# L6726a-5v.net
KiCad netlist of a schematic drawn in EAGLE
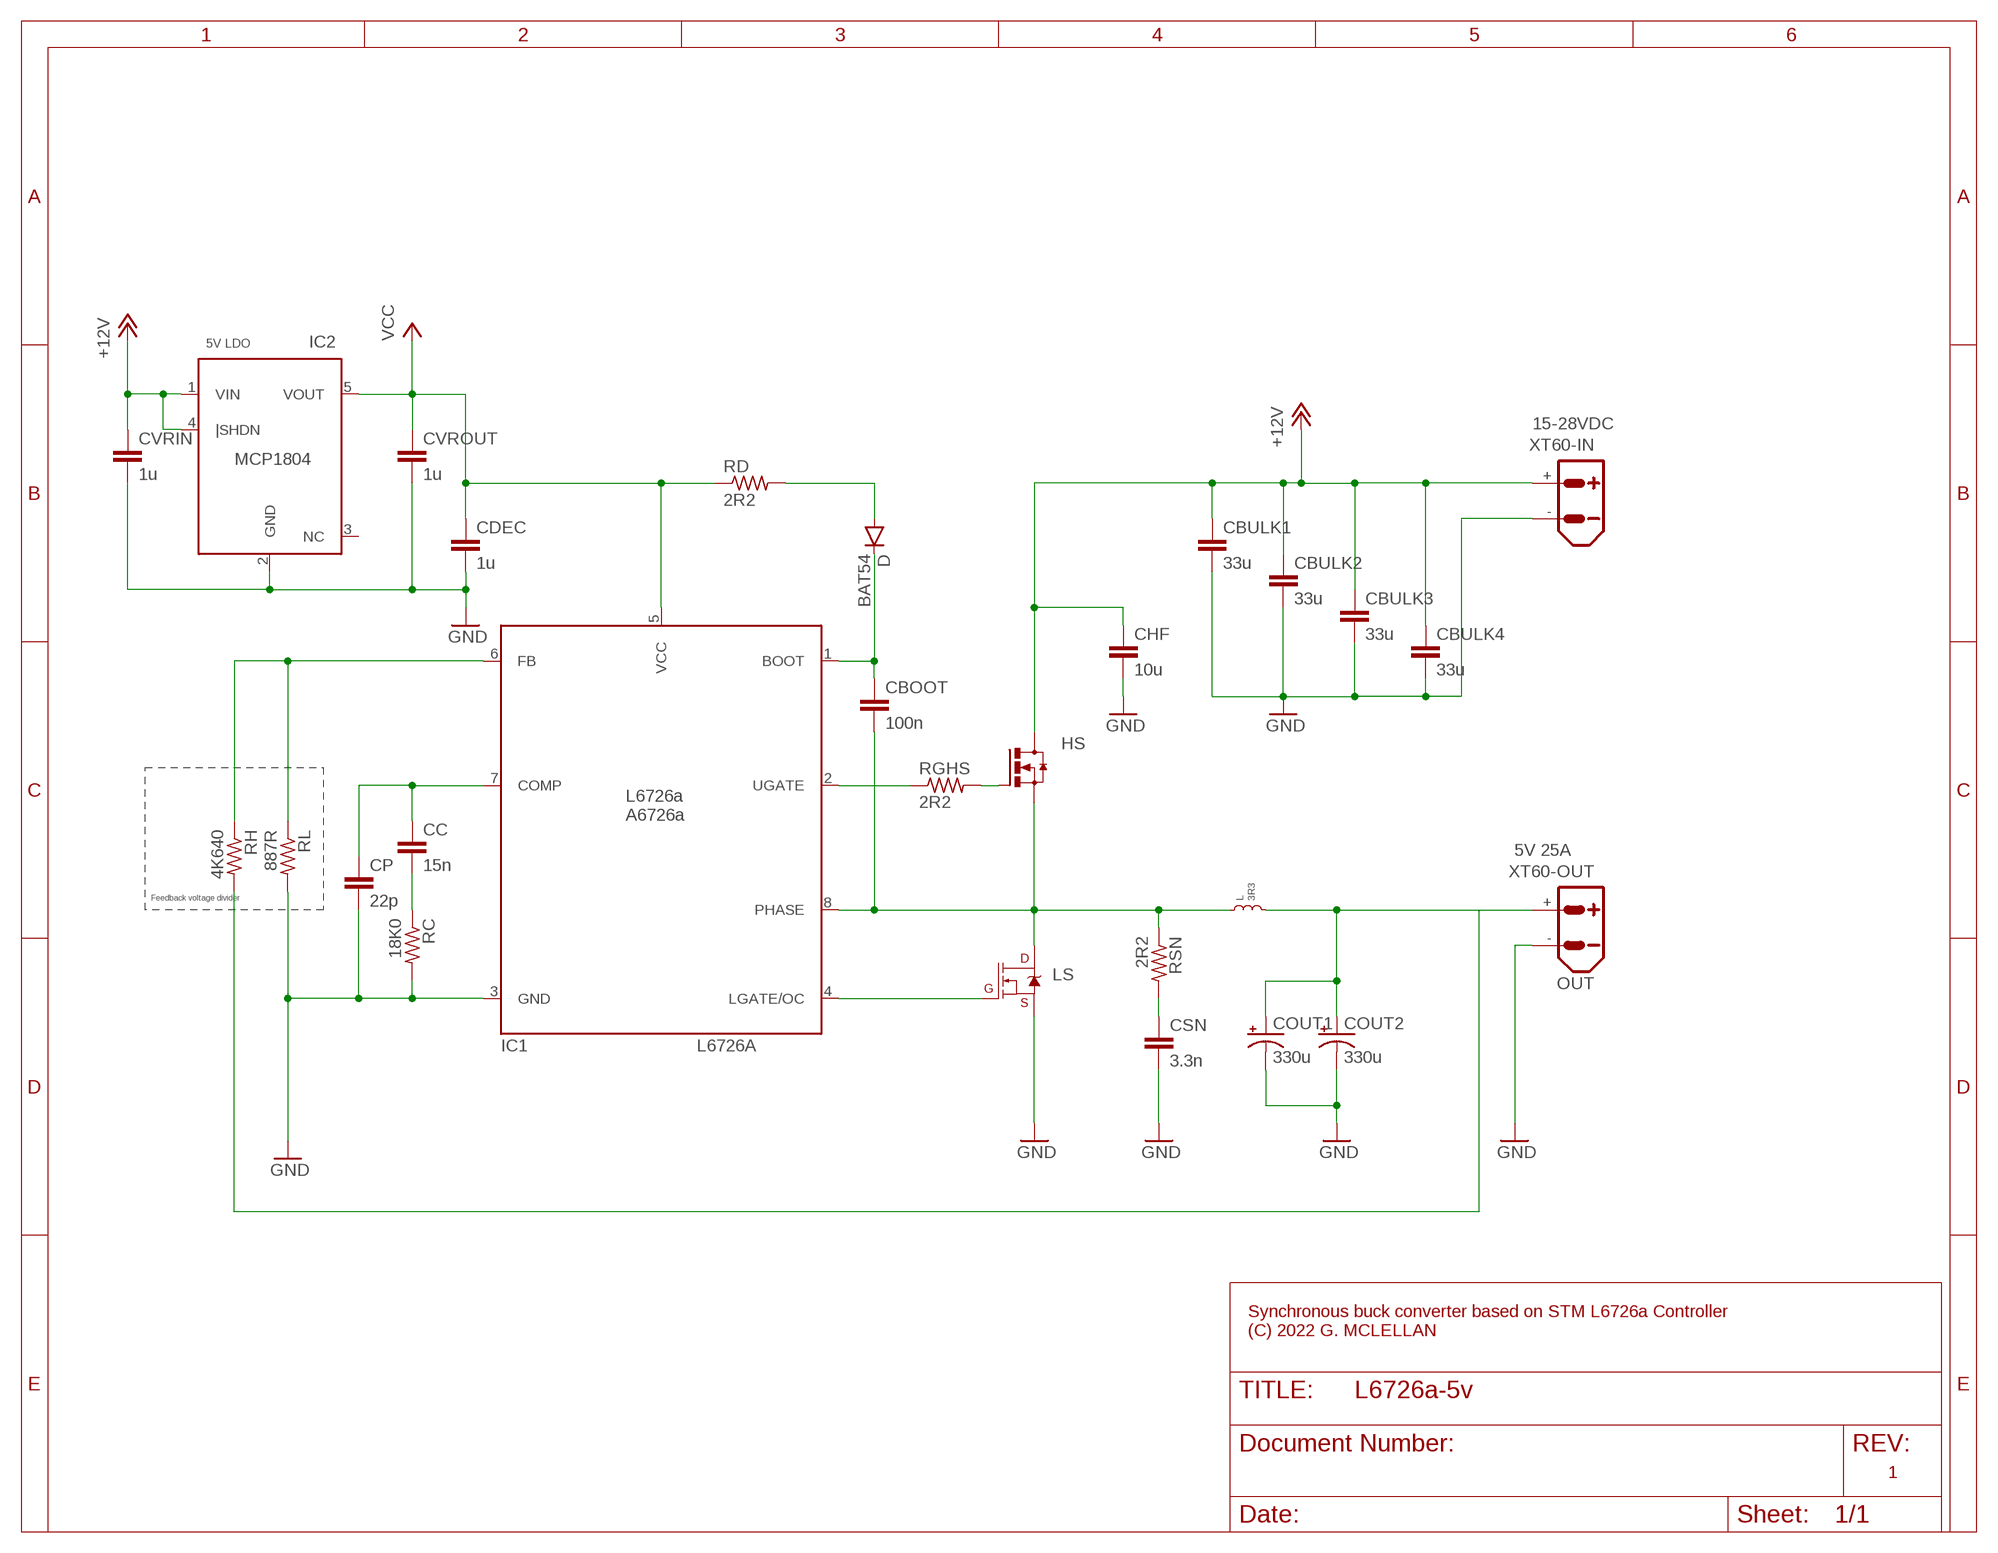
[diagram p0: schematic, sheet 1]

(export (version "E")
  (design (tool "Eeschema 10.0.6"))
  (components
    (comp (ref "CBOOT")
      (value "100n")
      (footprint "eagle-import:C0805")
      (libsource (lib "eagle-import") (part "C-EUC0805"))
    )
    (comp (ref "CBULK1")
      (value "33u")
      (footprint "eagle-import:C2220K")
      (libsource (lib "eagle-import") (part "C-EUC2220K"))
    )
    (comp (ref "CBULK2")
      (value "33u")
      (footprint "eagle-import:C2220K")
      (libsource (lib "eagle-import") (part "C-EUC2220K"))
    )
    (comp (ref "CBULK3")
      (value "33u")
      (footprint "eagle-import:C2220K")
      (libsource (lib "eagle-import") (part "C-EUC2220K"))
    )
    (comp (ref "CBULK4")
      (value "33u")
      (footprint "eagle-import:C2220K")
      (libsource (lib "eagle-import") (part "C-EUC2220K"))
    )
    (comp (ref "CC")
      (value "15n")
      (footprint "eagle-import:C0603")
      (libsource (lib "eagle-import") (part "C-EUC0603"))
    )
    (comp (ref "CDEC")
      (value "1u")
      (footprint "eagle-import:C0603")
      (libsource (lib "eagle-import") (part "C-EUC0603"))
    )
    (comp (ref "CHF")
      (value "10u")
      (footprint "eagle-import:C1206")
      (libsource (lib "eagle-import") (part "C-EUC1206"))
    )
    (comp (ref "COUT1")
      (value "330u")
      (footprint "eagle-import:SANYO-OSCON_SMD_C6")
      (libsource (lib "eagle-import") (part "CPOL-USSANYO_SMD_C6"))
    )
    (comp (ref "COUT2")
      (value "330u")
      (footprint "eagle-import:SANYO-OSCON_SMD_C6")
      (libsource (lib "eagle-import") (part "CPOL-USSANYO_SMD_C6"))
    )
    (comp (ref "CP")
      (value "22p")
      (footprint "eagle-import:C0603")
      (libsource (lib "eagle-import") (part "C-EUC0603"))
    )
    (comp (ref "CSN")
      (value "3.3n")
      (footprint "eagle-import:C0603")
      (libsource (lib "eagle-import") (part "C-EUC0603"))
    )
    (comp (ref "CVRIN")
      (value "1u")
      (footprint "eagle-import:C0603")
      (libsource (lib "eagle-import") (part "C-EUC0603"))
    )
    (comp (ref "CVROUT")
      (value "1u")
      (footprint "eagle-import:C0603")
      (libsource (lib "eagle-import") (part "C-EUC0603"))
    )
    (comp (ref "D")
      (value "BAT54")
      (footprint "eagle-import:SOD-123")
      (libsource (lib "eagle-import") (part "DIODESOD123"))
    )
    (comp (ref "HS")
      (value "N_MOSFET_POWERSO8")
      (footprint "eagle-import:POWERSO8")
      (libsource (lib "eagle-import") (part "N_MOSFET_POWERSO8"))
    )
    (comp (ref "IC1")
      (value "L6726A")
      (footprint "eagle-import:SO-08")
      (libsource (lib "eagle-import") (part "L6726A"))
    )
    (comp (ref "IC2")
      (value "MCP1804")
      (footprint "eagle-import:SOT23-5")
      (libsource (lib "eagle-import") (part "MCP1804"))
    )
    (comp (ref "L")
      (value "3R3")
      (footprint "eagle-import:XAL1010")
      (libsource (lib "eagle-import") (part "INDUCTOR.XAL1010"))
    )
    (comp (ref "LS")
      (value "MOSFET-NCH-FDS6630A")
      (footprint "eagle-import:SO08")
      (libsource (lib "eagle-import") (part "MOSFET-NCH-FDS6630A"))
    )
    (comp (ref "RC")
      (value "18K0")
      (footprint "eagle-import:R0603")
      (libsource (lib "eagle-import") (part "R-US_R0603"))
    )
    (comp (ref "RD")
      (value "2R2")
      (footprint "eagle-import:R0603")
      (libsource (lib "eagle-import") (part "R-US_R0603"))
    )
    (comp (ref "RGHS")
      (value "2R2")
      (footprint "eagle-import:R0805")
      (libsource (lib "eagle-import") (part "R-US_R0805"))
    )
    (comp (ref "RH")
      (value "4K640")
      (footprint "eagle-import:R0805")
      (libsource (lib "eagle-import") (part "R-US_R0805"))
    )
    (comp (ref "RL")
      (value "887R")
      (footprint "eagle-import:R0805")
      (libsource (lib "eagle-import") (part "R-US_R0805"))
    )
    (comp (ref "RSN")
      (value "2R2")
      (footprint "eagle-import:R0603")
      (libsource (lib "eagle-import") (part "R-US_R0603"))
    )
    (comp (ref "XT60-IN")
      (value "XT60PW-M")
      (footprint "eagle-import:XT60PW-M")
      (libsource (lib "eagle-import") (part "XT60PW-M"))
    )
    (comp (ref "XT60-OUT")
      (value "OUT")
      (footprint "eagle-import:XT60PW-M")
      (libsource (lib "eagle-import") (part "XT60PW-M"))
    )
  )
  (nets
    (net (code "1") (name "+12V") (class "Default")
      (node (ref "CBULK1") (pin "1") (pinfunction "1_1") (pintype "passive"))
      (node (ref "CBULK2") (pin "1") (pinfunction "1_1") (pintype "passive"))
      (node (ref "CBULK3") (pin "1") (pinfunction "1_1") (pintype "passive"))
      (node (ref "CBULK4") (pin "1") (pinfunction "1_1") (pintype "passive"))
      (node (ref "CHF") (pin "1") (pinfunction "1_1") (pintype "passive"))
      (node (ref "CVRIN") (pin "1") (pinfunction "1_1") (pintype "passive"))
      (node (ref "HS") (pin "5") (pinfunction "D_5") (pintype "passive"))
      (node (ref "HS") (pin "6") (pinfunction "D_6") (pintype "passive"))
      (node (ref "HS") (pin "7") (pinfunction "D_7") (pintype "passive"))
      (node (ref "HS") (pin "8") (pinfunction "D_8") (pintype "passive"))
      (node (ref "HS") (pin "PAD") (pinfunction "D_PAD") (pintype "passive"))
      (node (ref "IC2") (pin "1") (pinfunction "VIN_1") (pintype "power_in"))
      (node (ref "IC2") (pin "4") (pinfunction "|SHDN_4") (pintype "input"))
      (node (ref "XT60-IN") (pin "+") (pinfunction "+_+") (pintype "power_in"))
    )
    (net (code "2") (name "GND") (class "Default")
      (node (ref "CBULK1") (pin "2") (pinfunction "2_2") (pintype "passive"))
      (node (ref "CBULK2") (pin "2") (pinfunction "2_2") (pintype "passive"))
      (node (ref "CBULK3") (pin "2") (pinfunction "2_2") (pintype "passive"))
      (node (ref "CBULK4") (pin "2") (pinfunction "2_2") (pintype "passive"))
      (node (ref "CDEC") (pin "2") (pinfunction "2_2") (pintype "passive"))
      (node (ref "CHF") (pin "2") (pinfunction "2_2") (pintype "passive"))
      (node (ref "COUT1") (pin "-") (pinfunction "-_-") (pintype "passive"))
      (node (ref "COUT2") (pin "-") (pinfunction "-_-") (pintype "passive"))
      (node (ref "CP") (pin "2") (pinfunction "2_2") (pintype "passive"))
      (node (ref "CSN") (pin "2") (pinfunction "2_2") (pintype "passive"))
      (node (ref "CVRIN") (pin "2") (pinfunction "2_2") (pintype "passive"))
      (node (ref "CVROUT") (pin "2") (pinfunction "2_2") (pintype "passive"))
      (node (ref "IC1") (pin "3") (pinfunction "GND_3") (pintype "power_in"))
      (node (ref "IC2") (pin "2") (pinfunction "GND_2") (pintype "power_in"))
      (node (ref "LS") (pin "1") (pinfunction "S_1") (pintype "bidirectional"))
      (node (ref "LS") (pin "2") (pinfunction "S_2") (pintype "bidirectional"))
      (node (ref "LS") (pin "3") (pinfunction "S_3") (pintype "bidirectional"))
      (node (ref "RC") (pin "2") (pinfunction "2_2") (pintype "passive"))
      (node (ref "RL") (pin "2") (pinfunction "2_2") (pintype "passive"))
      (node (ref "XT60-IN") (pin "-") (pinfunction "-_-") (pintype "power_in"))
      (node (ref "XT60-OUT") (pin "-") (pinfunction "-_-") (pintype "power_in"))
    )
    (net (code "3") (name "Net-(CC-Pad2)") (class "Default")
      (node (ref "CC") (pin "2") (pinfunction "2_2") (pintype "passive"))
      (node (ref "RC") (pin "1") (pinfunction "1_1") (pintype "passive"))
    )
    (net (code "4") (name "Net-(CSN-Pad1)") (class "Default")
      (node (ref "CSN") (pin "1") (pinfunction "1_1") (pintype "passive"))
      (node (ref "RSN") (pin "2") (pinfunction "2_2") (pintype "passive"))
    )
    (net (code "5") (name "Net-(D-PadA)") (class "Default")
      (node (ref "D") (pin "A") (pinfunction "A_A") (pintype "passive"))
      (node (ref "RD") (pin "2") (pinfunction "2_2") (pintype "passive"))
    )
    (net (code "6") (name "Net-(HS-G)") (class "Default")
      (node (ref "HS") (pin "4") (pinfunction "G_4") (pintype "passive"))
      (node (ref "RGHS") (pin "2") (pinfunction "2_2") (pintype "passive"))
    )
    (net (code "7") (name "Net-(IC1-BOOT)") (class "Default")
      (node (ref "CBOOT") (pin "1") (pinfunction "1_1") (pintype "passive"))
      (node (ref "D") (pin "C") (pinfunction "C_C") (pintype "passive"))
      (node (ref "IC1") (pin "1") (pinfunction "BOOT_1") (pintype "power_in"))
    )
    (net (code "8") (name "Net-(IC1-COMP)") (class "Default")
      (node (ref "CC") (pin "1") (pinfunction "1_1") (pintype "passive"))
      (node (ref "CP") (pin "1") (pinfunction "1_1") (pintype "passive"))
      (node (ref "IC1") (pin "7") (pinfunction "COMP_7") (pintype "input"))
    )
    (net (code "9") (name "Net-(IC1-FB)") (class "Default")
      (node (ref "IC1") (pin "6") (pinfunction "FB_6") (pintype "input"))
      (node (ref "RH") (pin "1") (pinfunction "1_1") (pintype "passive"))
      (node (ref "RL") (pin "1") (pinfunction "1_1") (pintype "passive"))
    )
    (net (code "10") (name "Net-(IC1-LGATE{slash}OC)") (class "Default")
      (node (ref "IC1") (pin "4") (pinfunction "LGATE/OC_4") (pintype "output"))
      (node (ref "LS") (pin "4") (pinfunction "G_4") (pintype "bidirectional"))
    )
    (net (code "11") (name "Net-(IC1-PHASE)") (class "Default")
      (node (ref "CBOOT") (pin "2") (pinfunction "2_2") (pintype "passive"))
      (node (ref "HS") (pin "1") (pinfunction "S_1") (pintype "passive"))
      (node (ref "HS") (pin "2") (pinfunction "S_2") (pintype "passive"))
      (node (ref "HS") (pin "3") (pinfunction "S_3") (pintype "passive"))
      (node (ref "IC1") (pin "8") (pinfunction "PHASE_8") (pintype "input"))
      (node (ref "L") (pin "P$1") (pinfunction "1_P$1") (pintype "passive"))
      (node (ref "LS") (pin "5") (pinfunction "D_5") (pintype "bidirectional"))
      (node (ref "LS") (pin "6") (pinfunction "D_6") (pintype "bidirectional"))
      (node (ref "LS") (pin "7") (pinfunction "D_7") (pintype "bidirectional"))
      (node (ref "LS") (pin "8") (pinfunction "D_8") (pintype "bidirectional"))
      (node (ref "RSN") (pin "1") (pinfunction "1_1") (pintype "passive"))
    )
    (net (code "12") (name "Net-(IC1-UGATE)") (class "Default")
      (node (ref "IC1") (pin "2") (pinfunction "UGATE_2") (pintype "output"))
      (node (ref "RGHS") (pin "1") (pinfunction "1_1") (pintype "passive"))
    )
    (net (code "13") (name "Net-(L-2)") (class "Default")
      (node (ref "COUT1") (pin "+") (pinfunction "+_+") (pintype "passive"))
      (node (ref "COUT2") (pin "+") (pinfunction "+_+") (pintype "passive"))
      (node (ref "L") (pin "P$2") (pinfunction "2_P$2") (pintype "passive"))
      (node (ref "RH") (pin "2") (pinfunction "2_2") (pintype "passive"))
      (node (ref "XT60-OUT") (pin "+") (pinfunction "+_+") (pintype "power_in"))
    )
    (net (code "14") (name "VCC") (class "Default")
      (node (ref "CDEC") (pin "1") (pinfunction "1_1") (pintype "passive"))
      (node (ref "CVROUT") (pin "1") (pinfunction "1_1") (pintype "passive"))
      (node (ref "IC1") (pin "5") (pinfunction "VCC_5") (pintype "power_in"))
      (node (ref "IC2") (pin "5") (pinfunction "VOUT_5") (pintype "power_in"))
      (node (ref "RD") (pin "1") (pinfunction "1_1") (pintype "passive"))
    )
    (net (code "15") (name "unconnected-(IC2-NC-Pad3)") (class "Default")
      (node (ref "IC2") (pin "3") (pinfunction "NC_3") (pintype "no_connect"))
    )
  )
)
